# H17R0_Backend.net
KiCad netlist of a schematic drawn in Altium Designer
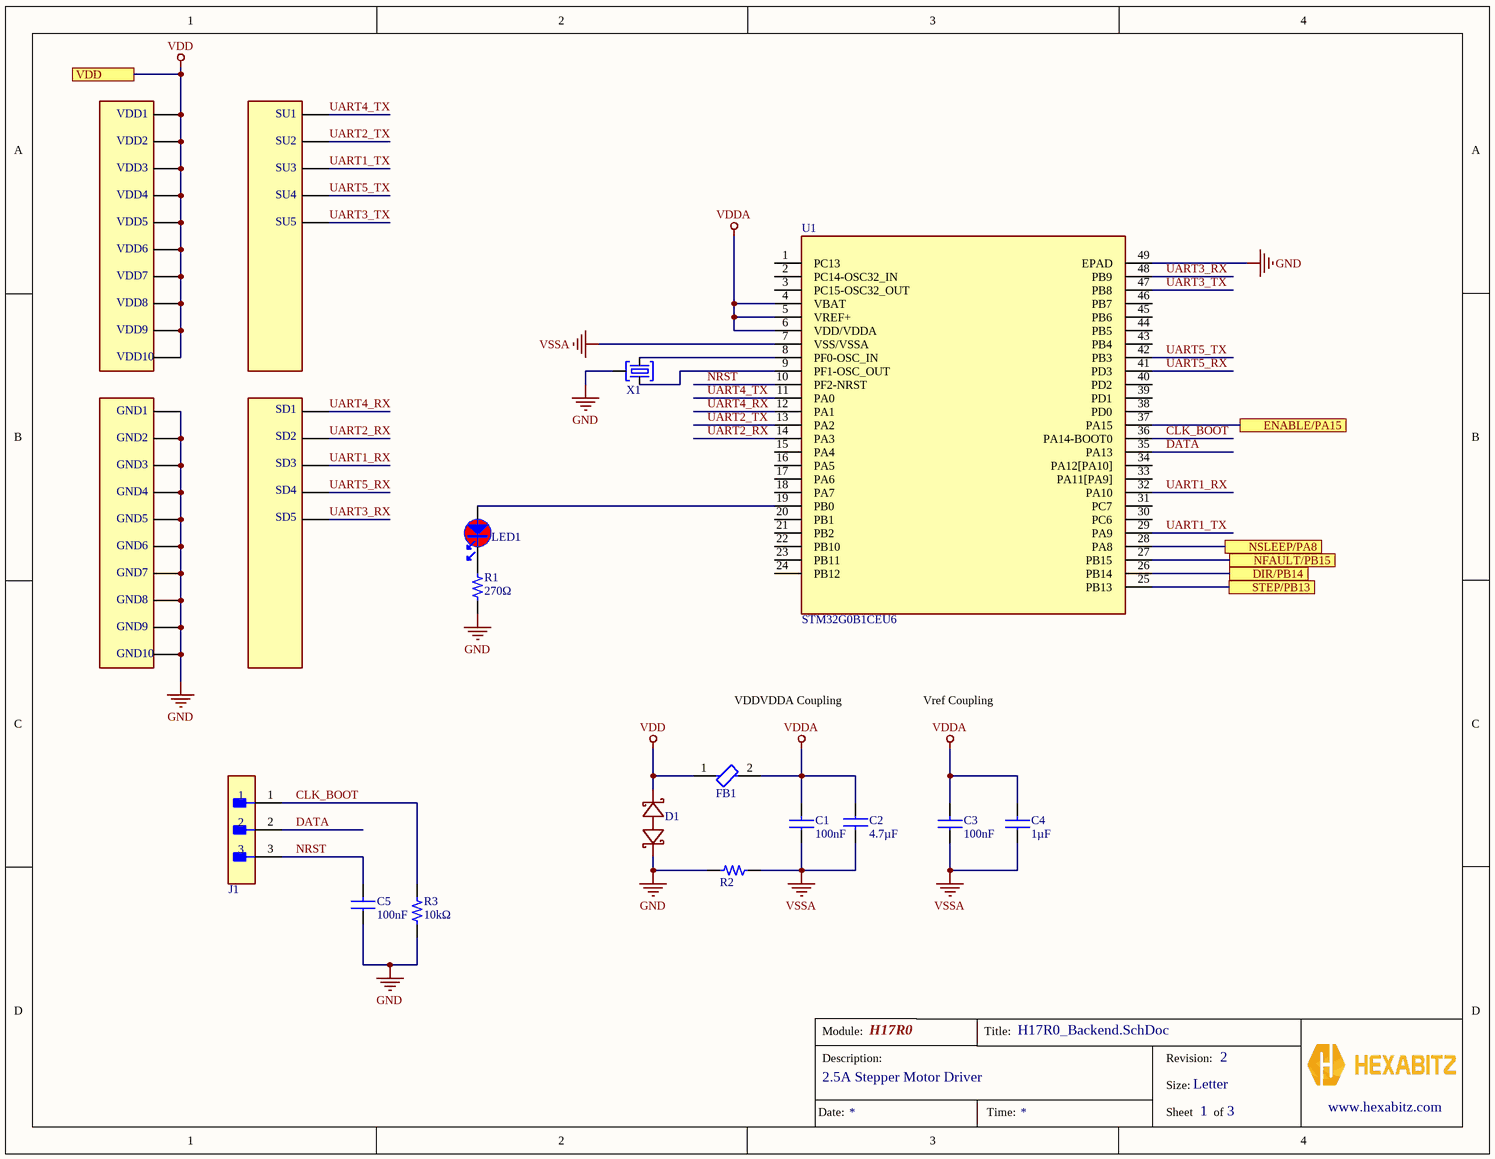
[diagram p0: H17R0_Backend.SchDoc]

(export (version "E")
  (design (tool "Eeschema 10.0.6"))
  (components
    (comp (ref "C1")
      (value "100nF")
      (footprint "C0603")
      (fields
        (field (name "MANUFACTURER") "Samsung Electro-Mechanics")
        (field (name "MANUFACTURER PART NUMBER") "CL10B104KA8NNNC")
        (field (name "TOLERANCE") "10%")
      )
      (libsource (lib "Hexabitz Altium Library") (part "generic Capacitor"))
    )
    (comp (ref "C2")
      (value "4.7µF")
      (footprint "C0805")
      (fields
        (field (name "MANUFACTURER") "Samsung Electro-Mechanics")
        (field (name "MANUFACTURER PART NUMBER") "CL21X475KAQNNNE")
        (field (name "TOLERANCE") "10%")
      )
      (libsource (lib "Hexabitz Altium Library") (part "generic Capacitor"))
    )
    (comp (ref "C3")
      (value "100nF")
      (footprint "C0603")
      (fields
        (field (name "MANUFACTURER") "Samsung Electro-Mechanics")
        (field (name "MANUFACTURER PART NUMBER") "CL10B104KA8NNNC")
        (field (name "TOLERANCE") "10%")
      )
      (libsource (lib "Hexabitz Altium Library") (part "generic Capacitor"))
    )
    (comp (ref "C4")
      (value "1µF")
      (footprint "C0805")
      (description "Ceramic Capacitor, Ceramic, 16V, 10% +Tol, 10% -Tol, X7R, 15% TC, 1uF, Surface Mount, 0805")
      (fields
        (field (name "MANUFACTURER") "Yageo Group")
        (field (name "MANUFACTURER PART NUMBER") "CC0805KKX7R7BB105")
      )
      (libsource (lib "Hexabitz Altium Library") (part "generic Capacitor"))
    )
    (comp (ref "C5")
      (value "100nF")
      (footprint "C0603")
      (fields
        (field (name "MANUFACTURER") "Samsung Electro-Mechanics")
        (field (name "MANUFACTURER PART NUMBER") "CL10B104KA8NNNC")
        (field (name "TOLERANCE") "10%")
      )
      (libsource (lib "Hexabitz Altium Library") (part "generic Capacitor"))
    )
    (comp (ref "D1")
      (value "CDSOD323-T03SC")
      (footprint "SOD2513X114N")
      (description "A 3V, 350W, bi-directional, standard capacitance, SOD323 pkg TVS Diode ¦ Bourns CDSOD323-T03SC")
      (fields (field (name "MANUFACTURER") "Bourns"))
      (libsource (lib "Hexabitz Altium Library") (part "CDSOD323-T03SC"))
    )
    (comp (ref "FB1")
      (value "MMZ1608Y300B")
      (footprint "FP-MMZ1608-0_8-MFG")
      (description "Ferrite Beads 0603 30ohms 1500mA Signal Line AEC-Q200")
      (fields
        (field (name "MANUFACTURER") "TDK")
        (field (name "MANUFACTURER PART NUMBER") "MMZ1608Y300BTD25")
      )
      (libsource (lib "Hexabitz Altium Library") (part "MMZ1608Y300B"))
    )
    (comp (ref "GND1")
      (value "HEXABIT_UART_PORT")
      (footprint "HEXABIT_POWER_PORT_D")
      (libsource (lib "hexabitz_connectors.Library") (part "HEXABIT_POWER_PORT_D"))
    )
    (comp (ref "GND2")
      (value "HEXABIT_UART_PORT")
      (footprint "HEXABIT_POWER_PORT_D")
      (libsource (lib "hexabitz_connectors.Library") (part "HEXABIT_POWER_PORT_D"))
    )
    (comp (ref "GND3")
      (value "HEXABIT_UART_PORT")
      (footprint "HEXABIT_POWER_PORT_D_300R")
      (libsource (lib "hexabitz_connectors.Library") (part "HEXABIT_POWER_PORT_D_300R"))
    )
    (comp (ref "GND4")
      (value "HEXABIT_UART_PORT")
      (footprint "HEXABIT_POWER_PORT_D")
      (libsource (lib "hexabitz_connectors.Library") (part "HEXABIT_POWER_PORT_D"))
    )
    (comp (ref "GND5")
      (value "HEXABIT_UART_PORT")
      (footprint "HEXABIT_POWER_PORT_D")
      (libsource (lib "hexabitz_connectors.Library") (part "HEXABIT_POWER_PORT_D"))
    )
    (comp (ref "GND6")
      (value "HEXABIT_UART_PORT")
      (footprint "HEXABIT_POWER_PORT_D")
      (libsource (lib "hexabitz_connectors.Library") (part "HEXABIT_POWER_PORT_D"))
    )
    (comp (ref "GND7")
      (value "HEXABIT_UART_PORT")
      (footprint "HEXABIT_POWER_PORT_D")
      (libsource (lib "hexabitz_connectors.Library") (part "HEXABIT_POWER_PORT_D"))
    )
    (comp (ref "GND8")
      (value "HEXABIT_UART_PORT")
      (footprint "HEXABIT_POWER_PORT_D_300L")
      (libsource (lib "hexabitz_connectors.Library") (part "HEXABIT_POWER_PORT_D_300L"))
    )
    (comp (ref "GND9")
      (value "HEXABIT_UART_PORT")
      (footprint "HEXABIT_POWER_PORT_D")
      (libsource (lib "hexabitz_connectors.Library") (part "HEXABIT_POWER_PORT_D"))
    )
    (comp (ref "GND10")
      (value "HEXABIT_UART_PORT")
      (footprint "HEXABIT_POWER_PORT_D")
      (libsource (lib "hexabitz_connectors.Library") (part "HEXABIT_POWER_PORT_D"))
    )
    (comp (ref "J1")
      (value "TSW-103-14-G-S")
      (footprint "FP-TSW-103-14-G-S-MFG")
      (description "CONN HEADER VERT 3POS 2.54MM")
      (libsource (lib "Altium Content Vault") (part "cd3439d6ef35ae5d9b27ec4fdd3e828"))
    )
    (comp (ref "LED1")
      (value "VLMS1300-GS08")
      (footprint "FP-6_541-5092_01-4-MFG")
      (description "LED Uni-Color Super Red 639nm 2-Pin Chip 0603(1608Metric) T/R")
      (fields (field (name "MANUFACTURER") "Vishay Semiconductors"))
      (libsource (lib "Hexabitz Altium Library") (part "VLMS1300-GS08"))
    )
    (comp (ref "R1")
      (value "270Ω")
      (footprint "R0603")
      (description "Res Thick Film 0603 270 Ohm 5% 0.1W(1/10W) ±200ppm/C Pad SMD Automotive T/R")
      (fields
        (field (name "MANUFACTURER") "Panasonic")
        (field (name "MANUFACTURER PART NUMBER") "ERJ-3GEYJ271V")
      )
      (libsource (lib "Hexabitz Altium Library") (part "generic Resistor"))
    )
    (comp (ref "R2")
      (value "Manufacturer Part Number")
      (footprint "R0603")
      (libsource (lib "") (part "generic Resistor_1"))
    )
    (comp (ref "R3")
      (value "10kΩ")
      (footprint "R0603")
      (description "100mW Thick Film Resistors ±100ppm/℃ ±1% 10kΩ 0603 Chip Resistor - Surface Mount ROHS")
      (fields
        (field (name "MANUFACTURER") "Yageo Group")
        (field (name "MANUFACTURER PART NUMBER") "RC0603FR-0710KL")
      )
      (libsource (lib "") (part "generic Resistor_2"))
    )
    (comp (ref "SD1")
      (value "HEXABIT_UART_PORT")
      (footprint "HEXABIT_UART_PORT_D")
      (libsource (lib "hexabitz_connectors.Library") (part "HEXABIT_UART_PORT_D"))
    )
    (comp (ref "SD2")
      (value "HEXABIT_UART_PORT")
      (footprint "HEXABIT_UART_PORT_D")
      (libsource (lib "hexabitz_connectors.Library") (part "HEXABIT_UART_PORT_D"))
    )
    (comp (ref "SD3")
      (value "HEXABIT_UART_PORT")
      (footprint "HEXABIT_UART_PORT_D")
      (libsource (lib "hexabitz_connectors.Library") (part "HEXABIT_UART_PORT_D"))
    )
    (comp (ref "SD4")
      (value "HEXABIT_UART_PORT")
      (footprint "HEXABIT_UART_PORT_D")
      (libsource (lib "hexabitz_connectors.Library") (part "HEXABIT_UART_PORT_D"))
    )
    (comp (ref "SD5")
      (value "HEXABIT_UART_PORT")
      (footprint "HEXABIT_UART_PORT_D")
      (libsource (lib "hexabitz_connectors.Library") (part "HEXABIT_UART_PORT_D"))
    )
    (comp (ref "SU1")
      (value "HEXABIT_UART_PORT")
      (footprint "HEXABIT_UART_PORT_U")
      (libsource (lib "hexabitz_connectors.Library") (part "HEXABIT_UART_PORT_U"))
    )
    (comp (ref "SU2")
      (value "HEXABIT_UART_PORT")
      (footprint "HEXABIT_UART_PORT_U")
      (libsource (lib "hexabitz_connectors.Library") (part "HEXABIT_UART_PORT_U"))
    )
    (comp (ref "SU3")
      (value "HEXABIT_UART_PORT")
      (footprint "HEXABIT_UART_PORT_U")
      (libsource (lib "hexabitz_connectors.Library") (part "HEXABIT_UART_PORT_U"))
    )
    (comp (ref "SU4")
      (value "HEXABIT_UART_PORT")
      (footprint "HEXABIT_UART_PORT_U")
      (libsource (lib "hexabitz_connectors.Library") (part "HEXABIT_UART_PORT_U"))
    )
    (comp (ref "SU5")
      (value "HEXABIT_UART_PORT")
      (footprint "HEXABIT_UART_PORT_U")
      (libsource (lib "hexabitz_connectors.Library") (part "HEXABIT_UART_PORT_U"))
    )
    (comp (ref "U1")
      (value "STM32G0B1CEU6")
      (footprint "QFN50P700X700X65-49N-D")
      (description "MCU 32-bit ARM Cortex M0+ RISC 512KB Flash 1.8V/2.5V/3.3V 48-Pin UFQFPN EP Tray")
      (fields
        (field (name "MANUFACTURER") "STMicroelectronics")
        (field (name "MANUFACTURER PART NUMBER") "STM32G0B1CEU6")
      )
      (libsource (lib "Hexabitz Altium Library") (part "STM32G0B1CEU6"))
    )
    (comp (ref "VDD1")
      (value "HEXABIT_UART_PORT")
      (footprint "HEXABIT_POWER_PORT_U")
      (libsource (lib "hexabitz_connectors.Library") (part "HEXABIT_POWER_PORT_U"))
    )
    (comp (ref "VDD2")
      (value "HEXABIT_UART_PORT")
      (footprint "HEXABIT_POWER_PORT_U")
      (libsource (lib "hexabitz_connectors.Library") (part "HEXABIT_POWER_PORT_U"))
    )
    (comp (ref "VDD3")
      (value "HEXABIT_UART_PORT")
      (footprint "HEXABIT_POWER_PORT_U_300R")
      (libsource (lib "hexabitz_connectors.Library") (part "HEXABIT_POWER_PORT_U_300R"))
    )
    (comp (ref "VDD4")
      (value "HEXABIT_UART_PORT")
      (footprint "HEXABIT_POWER_PORT_U")
      (libsource (lib "hexabitz_connectors.Library") (part "HEXABIT_POWER_PORT_U"))
    )
    (comp (ref "VDD5")
      (value "HEXABIT_UART_PORT")
      (footprint "HEXABIT_POWER_PORT_U")
      (libsource (lib "hexabitz_connectors.Library") (part "HEXABIT_POWER_PORT_U"))
    )
    (comp (ref "VDD6")
      (value "HEXABIT_UART_PORT")
      (footprint "HEXABIT_POWER_PORT_U")
      (libsource (lib "hexabitz_connectors.Library") (part "HEXABIT_POWER_PORT_U"))
    )
    (comp (ref "VDD7")
      (value "HEXABIT_UART_PORT")
      (footprint "HEXABIT_POWER_PORT_U")
      (libsource (lib "hexabitz_connectors.Library") (part "HEXABIT_POWER_PORT_U"))
    )
    (comp (ref "VDD8")
      (value "HEXABIT_UART_PORT")
      (footprint "HEXABIT_POWER_PORT_U_300L")
      (libsource (lib "hexabitz_connectors.Library") (part "HEXABIT_POWER_PORT_U_300L"))
    )
    (comp (ref "VDD9")
      (value "HEXABIT_UART_PORT")
      (footprint "HEXABIT_POWER_PORT_U")
      (libsource (lib "hexabitz_connectors.Library") (part "HEXABIT_POWER_PORT_U"))
    )
    (comp (ref "VDD10")
      (value "HEXABIT_UART_PORT")
      (footprint "HEXABIT_POWER_PORT_U")
      (libsource (lib "hexabitz_connectors.Library") (part "HEXABIT_POWER_PORT_U"))
    )
    (comp (ref "X1")
      (value "CSTCE8M00G52Z-R0")
      (footprint "XTALL_CSTCE8M00G52")
      (description "Ceramic Resonator 8MHz ±0.5% (Tol) ±0.2% (Stability) 10pF 40Ohm 3-Pin CSMD T/R")
      (fields (field (name "MANUFACTURER") "Murata") (field (name "TOLERANCE") "0.5%"))
      (libsource (lib "Hexabitz Altium Library") (part "CSTCE8M00G52Z-R0"))
    )
  )
  (nets
    (net (code "1") (name "/CLK_BOOT") (class "Default")
      (node (ref "J1") (pin "1") (pinfunction "1_1") (pintype "passive"))
      (node (ref "R3") (pin "1") (pinfunction "1_1") (pintype "passive"))
      (node (ref "U1") (pin "36") (pinfunction "PA14-BOOT0_36") (pintype "passive"))
    )
    (net (code "2") (name "/DATA") (class "Default")
      (node (ref "J1") (pin "2") (pinfunction "2_2") (pintype "passive"))
      (node (ref "U1") (pin "35") (pinfunction "PA13_35") (pintype "passive"))
    )
    (net (code "3") (name "/DIR{slash}PB14") (class "Default")
      (node (ref "U1") (pin "26") (pinfunction "PB14_26") (pintype "passive"))
    )
    (net (code "4") (name "/ENABLE{slash}PA15") (class "Default")
      (node (ref "U1") (pin "37") (pinfunction "PA15_37") (pintype "passive"))
    )
    (net (code "5") (name "/NFAULT{slash}PB15") (class "Default")
      (node (ref "U1") (pin "27") (pinfunction "PB15_27") (pintype "passive"))
    )
    (net (code "6") (name "/NRST") (class "Default")
      (node (ref "C5") (pin "2") (pinfunction "2_2") (pintype "passive"))
      (node (ref "J1") (pin "3") (pinfunction "3_3") (pintype "passive"))
      (node (ref "U1") (pin "10") (pinfunction "PF2-NRST_10") (pintype "passive"))
    )
    (net (code "7") (name "/NSLEEP{slash}PA8") (class "Default")
      (node (ref "U1") (pin "28") (pinfunction "PA8_28") (pintype "passive"))
    )
    (net (code "8") (name "/STEP{slash}PB13") (class "Default")
      (node (ref "U1") (pin "25") (pinfunction "PB13_25") (pintype "passive"))
    )
    (net (code "9") (name "/UART1_RX") (class "Default")
      (node (ref "SD3") (pin "UART_D") (pinfunction "UART_D_UART_D") (pintype "passive"))
      (node (ref "U1") (pin "32") (pinfunction "PA10_32") (pintype "passive"))
    )
    (net (code "10") (name "/UART1_TX") (class "Default")
      (node (ref "SU3") (pin "UART_U") (pinfunction "UART_U_UART_U") (pintype "passive"))
      (node (ref "U1") (pin "29") (pinfunction "PA9_29") (pintype "passive"))
    )
    (net (code "11") (name "/UART2_RX") (class "Default")
      (node (ref "SD2") (pin "UART_D") (pinfunction "UART_D_UART_D") (pintype "passive"))
      (node (ref "U1") (pin "14") (pinfunction "PA3_14") (pintype "passive"))
    )
    (net (code "12") (name "/UART2_TX") (class "Default")
      (node (ref "SU2") (pin "UART_U") (pinfunction "UART_U_UART_U") (pintype "passive"))
      (node (ref "U1") (pin "13") (pinfunction "PA2_13") (pintype "passive"))
    )
    (net (code "13") (name "/UART3_RX") (class "Default")
      (node (ref "SD5") (pin "UART_D") (pinfunction "UART_D_UART_D") (pintype "passive"))
      (node (ref "U1") (pin "48") (pinfunction "PB9_48") (pintype "passive"))
    )
    (net (code "14") (name "/UART3_TX") (class "Default")
      (node (ref "SU5") (pin "UART_U") (pinfunction "UART_U_UART_U") (pintype "passive"))
      (node (ref "U1") (pin "47") (pinfunction "PB8_47") (pintype "passive"))
    )
    (net (code "15") (name "/UART4_RX") (class "Default")
      (node (ref "SD1") (pin "UART_D") (pinfunction "UART_D_UART_D") (pintype "passive"))
      (node (ref "U1") (pin "12") (pinfunction "PA1_12") (pintype "passive"))
    )
    (net (code "16") (name "/UART4_TX") (class "Default")
      (node (ref "SU1") (pin "UART_U") (pinfunction "UART_U_UART_U") (pintype "passive"))
      (node (ref "U1") (pin "11") (pinfunction "PA0_11") (pintype "passive"))
    )
    (net (code "17") (name "/UART5_RX") (class "Default")
      (node (ref "SD4") (pin "UART_D") (pinfunction "UART_D_UART_D") (pintype "passive"))
      (node (ref "U1") (pin "41") (pinfunction "PD3_41") (pintype "passive"))
    )
    (net (code "18") (name "/UART5_TX") (class "Default")
      (node (ref "SU4") (pin "UART_U") (pinfunction "UART_U_UART_U") (pintype "passive"))
      (node (ref "U1") (pin "42") (pinfunction "PB3_42") (pintype "passive"))
    )
    (net (code "19") (name "GND") (class "Default")
      (node (ref "C5") (pin "1") (pinfunction "1_1") (pintype "passive"))
      (node (ref "D1") (pin "1") (pinfunction "A_1") (pintype "passive"))
      (node (ref "GND1") (pin "Pwr_D") (pinfunction "Pwr_D_Pwr_D") (pintype "passive"))
      (node (ref "GND10") (pin "Pwr_D") (pinfunction "Pwr_D_Pwr_D") (pintype "passive"))
      (node (ref "GND2") (pin "Pwr_D") (pinfunction "Pwr_D_Pwr_D") (pintype "passive"))
      (node (ref "GND3") (pin "Pwr_D") (pinfunction "Pwr_D_Pwr_D") (pintype "passive"))
      (node (ref "GND4") (pin "Pwr_D") (pinfunction "Pwr_D_Pwr_D") (pintype "passive"))
      (node (ref "GND5") (pin "Pwr_D") (pinfunction "Pwr_D_Pwr_D") (pintype "passive"))
      (node (ref "GND6") (pin "Pwr_D") (pinfunction "Pwr_D_Pwr_D") (pintype "passive"))
      (node (ref "GND7") (pin "Pwr_D") (pinfunction "Pwr_D_Pwr_D") (pintype "passive"))
      (node (ref "GND8") (pin "Pwr_D") (pinfunction "Pwr_D_Pwr_D") (pintype "passive"))
      (node (ref "GND9") (pin "Pwr_D") (pinfunction "Pwr_D_Pwr_D") (pintype "passive"))
      (node (ref "R1") (pin "1") (pinfunction "1_1") (pintype "passive"))
      (node (ref "R2") (pin "1") (pinfunction "1_1") (pintype "passive"))
      (node (ref "R3") (pin "2") (pinfunction "2_2") (pintype "passive"))
      (node (ref "U1") (pin "49") (pinfunction "EPAD_49") (pintype "passive"))
      (node (ref "X1") (pin "P$2") (pinfunction "2_P$2") (pintype "passive"))
    )
    (net (code "20") (name "Net-(LED1-Pad1)") (class "Default")
      (node (ref "LED1") (pin "1") (pintype "passive"))
      (node (ref "R1") (pin "2") (pinfunction "2_2") (pintype "passive"))
    )
    (net (code "21") (name "Net-(U1-PB0)") (class "Default")
      (node (ref "LED1") (pin "2") (pintype "passive"))
      (node (ref "U1") (pin "19") (pinfunction "PB0_19") (pintype "passive"))
    )
    (net (code "22") (name "Net-(U1-PF0-OSC_IN)") (class "Default")
      (node (ref "U1") (pin "8") (pinfunction "PF0-OSC_IN_8") (pintype "passive"))
      (node (ref "X1") (pin "P$3") (pinfunction "3_P$3") (pintype "passive"))
    )
    (net (code "23") (name "Net-(U1-PF1-OSC_OUT)") (class "Default")
      (node (ref "U1") (pin "9") (pinfunction "PF1-OSC_OUT_9") (pintype "passive"))
      (node (ref "X1") (pin "P$1") (pinfunction "1_P$1") (pintype "passive"))
    )
    (net (code "24") (name "VDD") (class "Default")
      (node (ref "D1") (pin "2") (pinfunction "C_2") (pintype "passive"))
      (node (ref "FB1") (pin "1") (pinfunction "1_1") (pintype "passive"))
      (node (ref "VDD1") (pin "Pwr_U") (pinfunction "Pwr_U_Pwr_U") (pintype "passive"))
      (node (ref "VDD10") (pin "Pwr_U") (pinfunction "Pwr_U_Pwr_U") (pintype "passive"))
      (node (ref "VDD2") (pin "Pwr_U") (pinfunction "Pwr_U_Pwr_U") (pintype "passive"))
      (node (ref "VDD3") (pin "Pwr_U") (pinfunction "Pwr_U_Pwr_U") (pintype "passive"))
      (node (ref "VDD4") (pin "Pwr_U") (pinfunction "Pwr_U_Pwr_U") (pintype "passive"))
      (node (ref "VDD5") (pin "Pwr_U") (pinfunction "Pwr_U_Pwr_U") (pintype "passive"))
      (node (ref "VDD6") (pin "Pwr_U") (pinfunction "Pwr_U_Pwr_U") (pintype "passive"))
      (node (ref "VDD7") (pin "Pwr_U") (pinfunction "Pwr_U_Pwr_U") (pintype "passive"))
      (node (ref "VDD8") (pin "Pwr_U") (pinfunction "Pwr_U_Pwr_U") (pintype "passive"))
      (node (ref "VDD9") (pin "Pwr_U") (pinfunction "Pwr_U_Pwr_U") (pintype "passive"))
    )
    (net (code "25") (name "VDDA") (class "Default")
      (node (ref "C1") (pin "2") (pinfunction "2_2") (pintype "passive"))
      (node (ref "C2") (pin "1") (pinfunction "1_1") (pintype "passive"))
      (node (ref "C3") (pin "2") (pinfunction "2_2") (pintype "passive"))
      (node (ref "C4") (pin "2") (pinfunction "2_2") (pintype "passive"))
      (node (ref "FB1") (pin "2") (pinfunction "2_2") (pintype "passive"))
      (node (ref "U1") (pin "4") (pinfunction "VBAT_4") (pintype "passive"))
      (node (ref "U1") (pin "5") (pinfunction "VREF+_5") (pintype "passive"))
      (node (ref "U1") (pin "6") (pinfunction "VDD/VDDA_6") (pintype "passive"))
    )
    (net (code "26") (name "VSSA") (class "Default")
      (node (ref "C1") (pin "1") (pinfunction "1_1") (pintype "passive"))
      (node (ref "C2") (pin "2") (pinfunction "2_2") (pintype "passive"))
      (node (ref "C3") (pin "1") (pinfunction "1_1") (pintype "passive"))
      (node (ref "C4") (pin "1") (pinfunction "1_1") (pintype "passive"))
      (node (ref "R2") (pin "2") (pinfunction "2_2") (pintype "passive"))
      (node (ref "U1") (pin "7") (pinfunction "VSS/VSSA_7") (pintype "passive"))
    )
    (net (code "27") (name "unconnected-(U1-PA4-Pad15)") (class "Default")
      (node (ref "U1") (pin "15") (pinfunction "PA4_15") (pintype "passive"))
    )
    (net (code "28") (name "unconnected-(U1-PA5-Pad16)") (class "Default")
      (node (ref "U1") (pin "16") (pinfunction "PA5_16") (pintype "passive"))
    )
    (net (code "29") (name "unconnected-(U1-PA6-Pad17)") (class "Default")
      (node (ref "U1") (pin "17") (pinfunction "PA6_17") (pintype "passive"))
    )
    (net (code "30") (name "unconnected-(U1-PA7-Pad18)") (class "Default")
      (node (ref "U1") (pin "18") (pinfunction "PA7_18") (pintype "passive"))
    )
    (net (code "31") (name "unconnected-(U1-PA11[PA9]-Pad33)") (class "Default")
      (node (ref "U1") (pin "33") (pinfunction "PA11[PA9]_33") (pintype "passive"))
    )
    (net (code "32") (name "unconnected-(U1-PA12[PA10]-Pad34)") (class "Default")
      (node (ref "U1") (pin "34") (pinfunction "PA12[PA10]_34") (pintype "passive"))
    )
    (net (code "33") (name "unconnected-(U1-PB1-Pad20)") (class "Default")
      (node (ref "U1") (pin "20") (pinfunction "PB1_20") (pintype "passive"))
    )
    (net (code "34") (name "unconnected-(U1-PB2-Pad21)") (class "Default")
      (node (ref "U1") (pin "21") (pinfunction "PB2_21") (pintype "passive"))
    )
    (net (code "35") (name "unconnected-(U1-PB4-Pad43)") (class "Default")
      (node (ref "U1") (pin "43") (pinfunction "PB4_43") (pintype "passive"))
    )
    (net (code "36") (name "unconnected-(U1-PB5-Pad44)") (class "Default")
      (node (ref "U1") (pin "44") (pinfunction "PB5_44") (pintype "passive"))
    )
    (net (code "37") (name "unconnected-(U1-PB6-Pad45)") (class "Default")
      (node (ref "U1") (pin "45") (pinfunction "PB6_45") (pintype "passive"))
    )
    (net (code "38") (name "unconnected-(U1-PB7-Pad46)") (class "Default")
      (node (ref "U1") (pin "46") (pinfunction "PB7_46") (pintype "passive"))
    )
    (net (code "39") (name "unconnected-(U1-PB10-Pad22)") (class "Default")
      (node (ref "U1") (pin "22") (pinfunction "PB10_22") (pintype "passive"))
    )
    (net (code "40") (name "unconnected-(U1-PB11-Pad23)") (class "Default")
      (node (ref "U1") (pin "23") (pinfunction "PB11_23") (pintype "passive"))
    )
    (net (code "41") (name "unconnected-(U1-PB12-Pad24)") (class "Default")
      (node (ref "U1") (pin "24") (pinfunction "PB12_24") (pintype "passive"))
    )
    (net (code "42") (name "unconnected-(U1-PC6-Pad30)") (class "Default")
      (node (ref "U1") (pin "30") (pinfunction "PC6_30") (pintype "passive"))
    )
    (net (code "43") (name "unconnected-(U1-PC7-Pad31)") (class "Default")
      (node (ref "U1") (pin "31") (pinfunction "PC7_31") (pintype "passive"))
    )
    (net (code "44") (name "unconnected-(U1-PC13-Pad1)") (class "Default")
      (node (ref "U1") (pin "1") (pinfunction "PC13_1") (pintype "passive"))
    )
    (net (code "45") (name "unconnected-(U1-PC14-OSC32_IN-Pad2)") (class "Default")
      (node (ref "U1") (pin "2") (pinfunction "PC14-OSC32_IN_2") (pintype "passive"))
    )
    (net (code "46") (name "unconnected-(U1-PC15-OSC32_OUT-Pad3)") (class "Default")
      (node (ref "U1") (pin "3") (pinfunction "PC15-OSC32_OUT_3") (pintype "passive"))
    )
    (net (code "47") (name "unconnected-(U1-PD0-Pad38)") (class "Default")
      (node (ref "U1") (pin "38") (pinfunction "PD0_38") (pintype "passive"))
    )
    (net (code "48") (name "unconnected-(U1-PD1-Pad39)") (class "Default")
      (node (ref "U1") (pin "39") (pinfunction "PD1_39") (pintype "passive"))
    )
    (net (code "49") (name "unconnected-(U1-PD2-Pad40)") (class "Default")
      (node (ref "U1") (pin "40") (pinfunction "PD2_40") (pintype "passive"))
    )
  )
)
